# Fdbk_2.net
KiCad netlist of a schematic drawn in Altium Designer
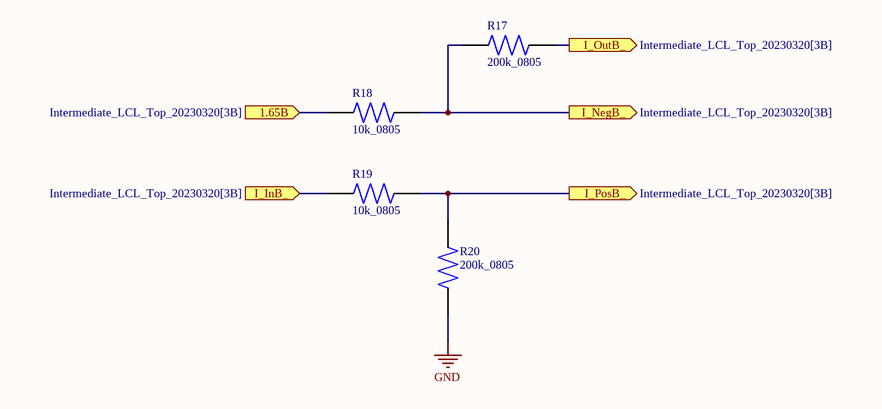
[diagram p0: Fdbk_2.SchDoc]

(export (version "E")
  (design (tool "Eeschema 10.0.6"))
  (components
    (comp (ref "R17")
      (value "200k_0805")
      (footprint "FYP_Components:0805 Resistor")
      (description "SMD Chip Resistor, 200 kohm, ± 1%, 125 mW, 0805 [2012 Metric], Thick Film, General Purpose")
      (fields (field (name "MF") "Bourns") (field (name "MP") "CRE2512-FZ-R007E-3"))
      (libsource (lib "FYP_Components") (part "CRCW0805200KFKEA"))
    )
    (comp (ref "R18")
      (value "10k_0805")
      (footprint "FYP_Components:0805 Resistor")
      (description "SMD Chip Resistor, 10 kohm, ± 1%, 125 mW, 0805 [2012 Metric], Thick Film, General Purpose")
      (fields (field (name "MF") "Bourns") (field (name "MP") "CRE2512-FZ-R007E-3"))
      (libsource (lib "FYP_Components") (part "CRCW080510K0FKEA"))
    )
    (comp (ref "R19")
      (value "10k_0805")
      (footprint "FYP_Components:0805 Resistor")
      (description "SMD Chip Resistor, 10 kohm, ± 1%, 125 mW, 0805 [2012 Metric], Thick Film, General Purpose")
      (fields (field (name "MF") "Bourns") (field (name "MP") "CRE2512-FZ-R007E-3"))
      (libsource (lib "FYP_Components") (part "CRCW080510K0FKEA"))
    )
    (comp (ref "R20")
      (value "200k_0805")
      (footprint "FYP_Components:0805 Resistor")
      (description "SMD Chip Resistor, 200 kohm, ± 1%, 125 mW, 0805 [2012 Metric], Thick Film, General Purpose")
      (fields (field (name "MF") "Bourns") (field (name "MP") "CRE2512-FZ-R007E-3"))
      (libsource (lib "FYP_Components") (part "CRCW0805200KFKEA"))
    )
  )
  (nets
    (net (code "1") (name "/1.65B") (class "Default")
      (node (ref "R18") (pin "1") (pinfunction "1_1") (pintype "passive"))
    )
    (net (code "2") (name "/I_InB_") (class "Default")
      (node (ref "R19") (pin "1") (pinfunction "1_1") (pintype "passive"))
    )
    (net (code "3") (name "/I_NegB_") (class "Default")
      (node (ref "R17") (pin "1") (pinfunction "1_1") (pintype "passive"))
      (node (ref "R18") (pin "2") (pinfunction "2_2") (pintype "passive"))
    )
    (net (code "4") (name "/I_OutB_") (class "Default")
      (node (ref "R17") (pin "2") (pinfunction "2_2") (pintype "passive"))
    )
    (net (code "5") (name "/I_PosB_") (class "Default")
      (node (ref "R19") (pin "2") (pinfunction "2_2") (pintype "passive"))
      (node (ref "R20") (pin "2") (pinfunction "2_2") (pintype "passive"))
    )
    (net (code "6") (name "GND") (class "Default")
      (node (ref "R20") (pin "1") (pinfunction "1_1") (pintype "passive"))
    )
  )
)
